# top_3-28-21m.net
KiCad netlist of a schematic drawn in EAGLE
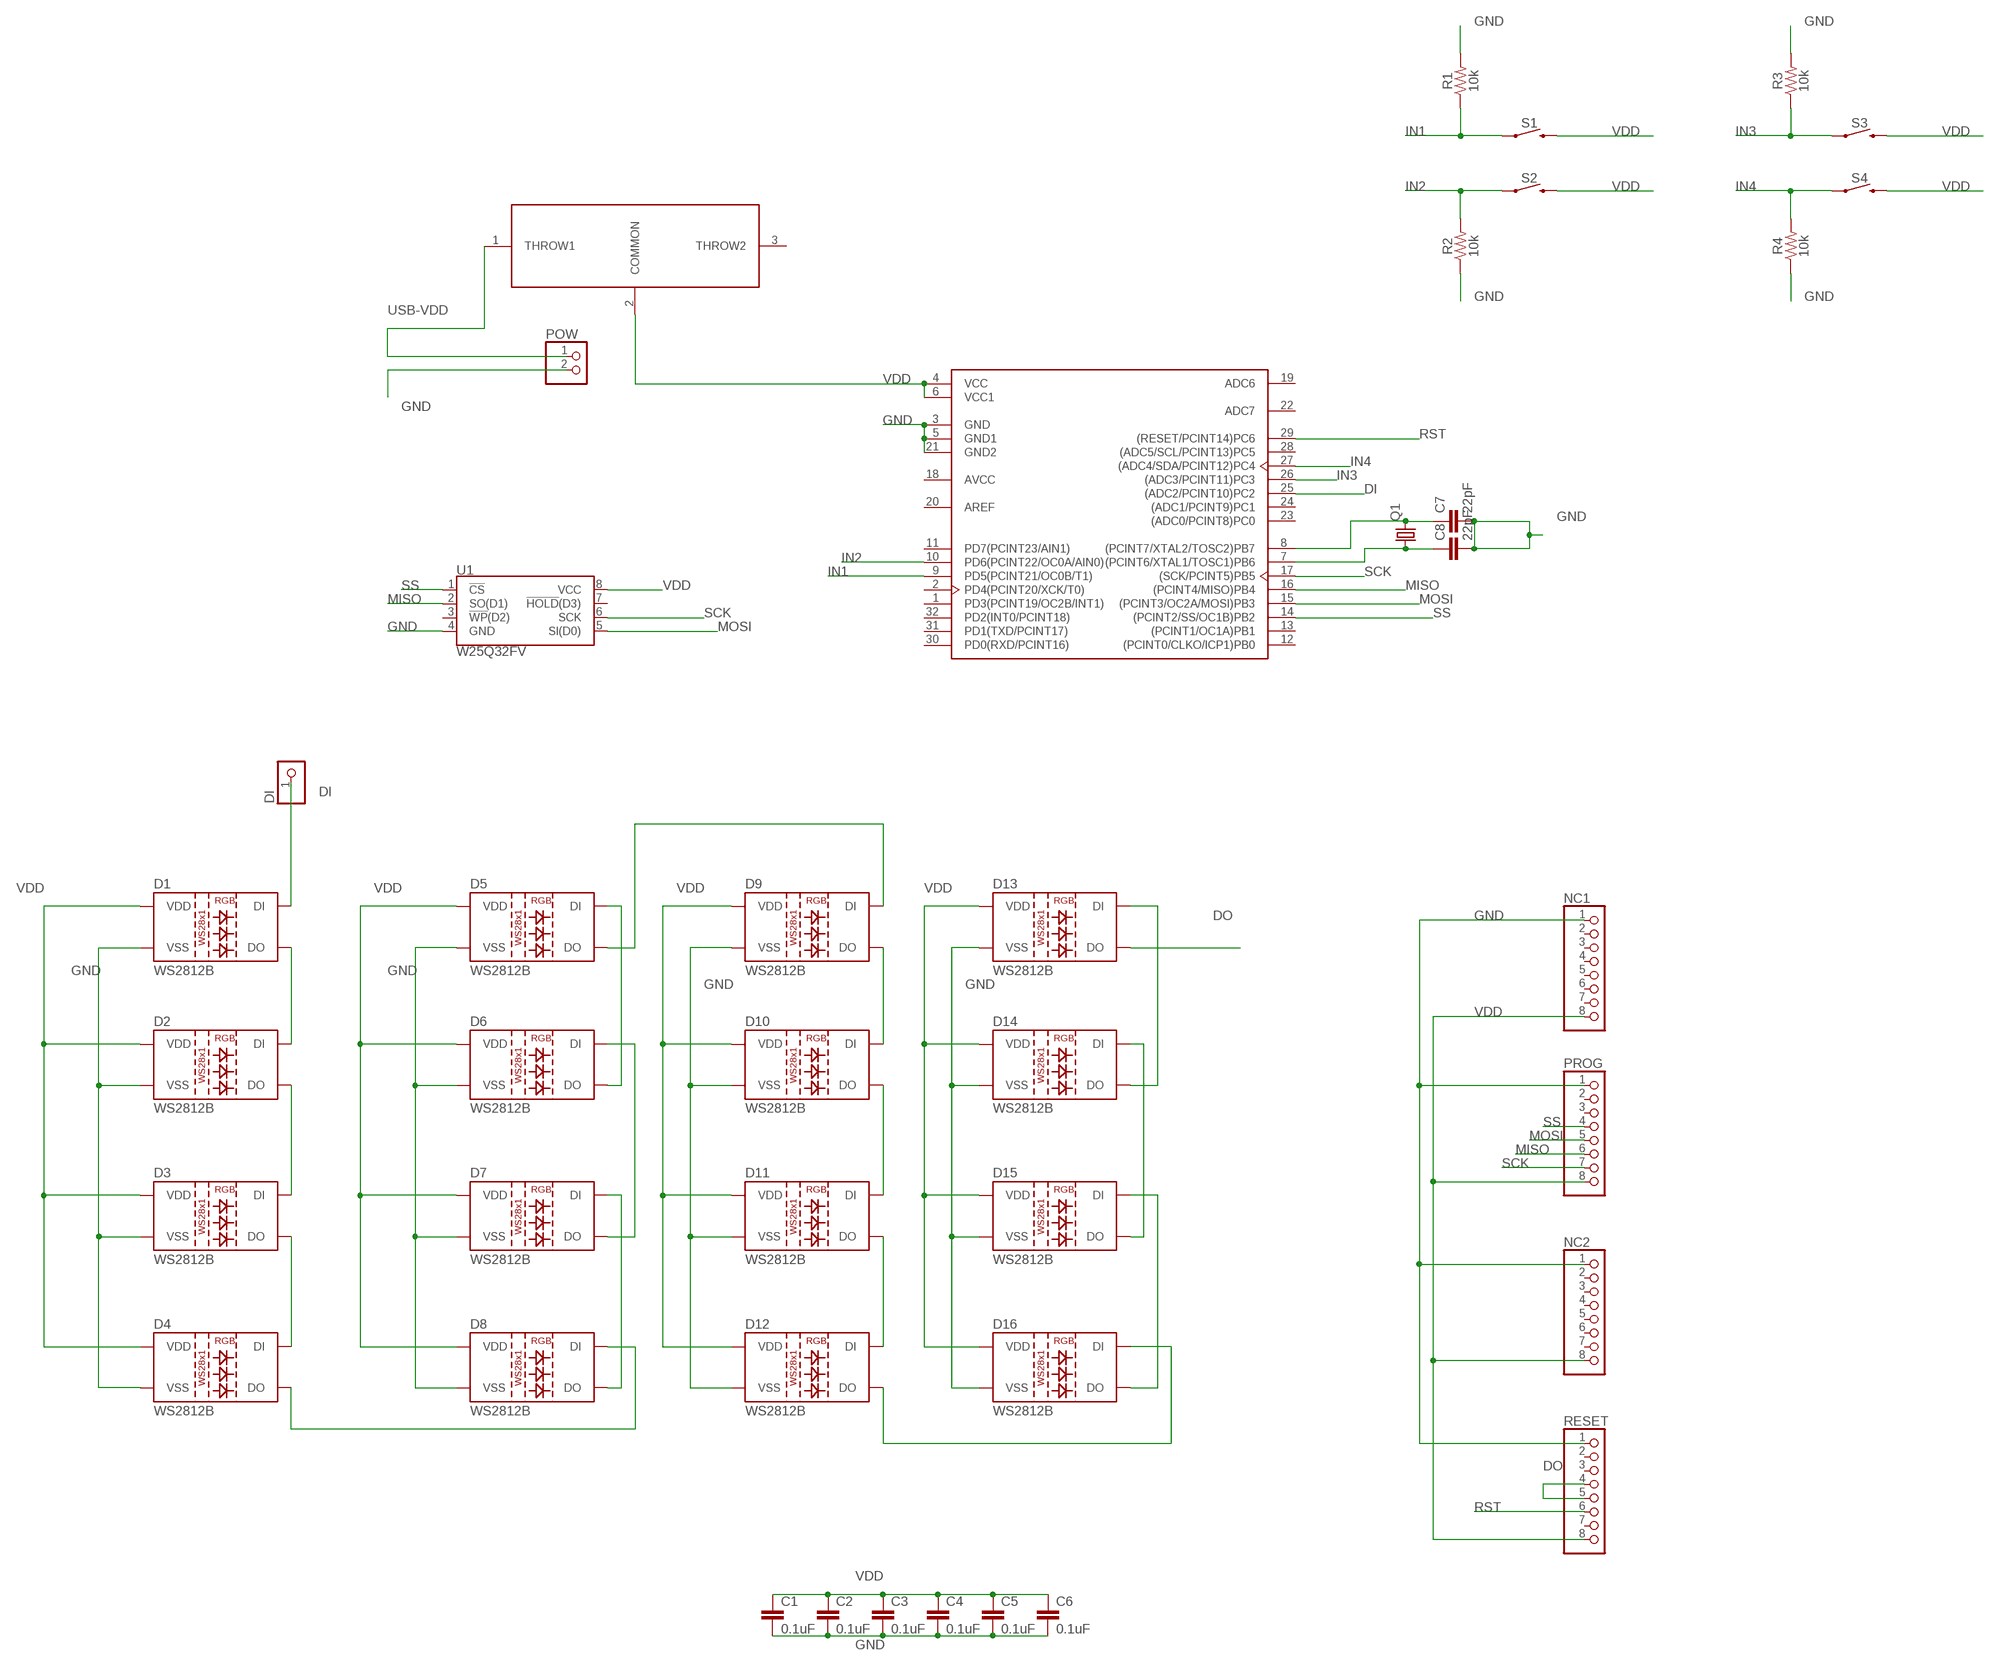
[diagram p0: schematic, sheet 1]

(export (version "E")
  (design (tool "Eeschema 10.0.6"))
  (components
    (comp (ref "C1")
      (value "0.1uF")
      (footprint "eagle-import:0603")
      (libsource (lib "eagle-import") (part "0.1UF-0603-25V-5%"))
    )
    (comp (ref "C2")
      (value "0.1uF")
      (footprint "eagle-import:0603")
      (libsource (lib "eagle-import") (part "0.1UF-0603-25V-5%"))
    )
    (comp (ref "C3")
      (value "0.1uF")
      (footprint "eagle-import:0603")
      (libsource (lib "eagle-import") (part "0.1UF-0603-25V-5%"))
    )
    (comp (ref "C4")
      (value "0.1uF")
      (footprint "eagle-import:0603")
      (libsource (lib "eagle-import") (part "0.1UF-0603-25V-5%"))
    )
    (comp (ref "C5")
      (value "0.1uF")
      (footprint "eagle-import:0603")
      (libsource (lib "eagle-import") (part "0.1UF-0603-25V-5%"))
    )
    (comp (ref "C6")
      (value "0.1uF")
      (footprint "eagle-import:0603")
      (libsource (lib "eagle-import") (part "0.1UF-0603-25V-5%"))
    )
    (comp (ref "C7")
      (value "22pF")
      (footprint "eagle-import:0805")
      (libsource (lib "eagle-import") (part "1.0UF-0805-25V-(+80/-20%)"))
    )
    (comp (ref "C8")
      (value "22pF")
      (footprint "eagle-import:0805")
      (libsource (lib "eagle-import") (part "1.0UF-0805-25V-(+80/-20%)"))
    )
    (comp (ref "D1")
      (value "WS2812B")
      (footprint "eagle-import:WS2812B")
      (libsource (lib "eagle-import") (part "WS2812B"))
    )
    (comp (ref "D2")
      (value "WS2812B")
      (footprint "eagle-import:WS2812B")
      (libsource (lib "eagle-import") (part "WS2812B"))
    )
    (comp (ref "D3")
      (value "WS2812B")
      (footprint "eagle-import:WS2812B")
      (libsource (lib "eagle-import") (part "WS2812B"))
    )
    (comp (ref "D4")
      (value "WS2812B")
      (footprint "eagle-import:WS2812B")
      (libsource (lib "eagle-import") (part "WS2812B"))
    )
    (comp (ref "D5")
      (value "WS2812B")
      (footprint "eagle-import:WS2812B")
      (libsource (lib "eagle-import") (part "WS2812B"))
    )
    (comp (ref "D6")
      (value "WS2812B")
      (footprint "eagle-import:WS2812B")
      (libsource (lib "eagle-import") (part "WS2812B"))
    )
    (comp (ref "D7")
      (value "WS2812B")
      (footprint "eagle-import:WS2812B")
      (libsource (lib "eagle-import") (part "WS2812B"))
    )
    (comp (ref "D8")
      (value "WS2812B")
      (footprint "eagle-import:WS2812B")
      (libsource (lib "eagle-import") (part "WS2812B"))
    )
    (comp (ref "D9")
      (value "WS2812B")
      (footprint "eagle-import:WS2812B")
      (libsource (lib "eagle-import") (part "WS2812B"))
    )
    (comp (ref "D10")
      (value "WS2812B")
      (footprint "eagle-import:WS2812B")
      (libsource (lib "eagle-import") (part "WS2812B"))
    )
    (comp (ref "D11")
      (value "WS2812B")
      (footprint "eagle-import:WS2812B")
      (libsource (lib "eagle-import") (part "WS2812B"))
    )
    (comp (ref "D12")
      (value "WS2812B")
      (footprint "eagle-import:WS2812B")
      (libsource (lib "eagle-import") (part "WS2812B"))
    )
    (comp (ref "D13")
      (value "WS2812B")
      (footprint "eagle-import:WS2812B")
      (libsource (lib "eagle-import") (part "WS2812B"))
    )
    (comp (ref "D14")
      (value "WS2812B")
      (footprint "eagle-import:WS2812B")
      (libsource (lib "eagle-import") (part "WS2812B"))
    )
    (comp (ref "D15")
      (value "WS2812B")
      (footprint "eagle-import:WS2812B")
      (libsource (lib "eagle-import") (part "WS2812B"))
    )
    (comp (ref "D16")
      (value "WS2812B")
      (footprint "eagle-import:WS2812B")
      (libsource (lib "eagle-import") (part "WS2812B"))
    )
    (comp (ref "DI")
      (value "PINHD-1X1")
      (footprint "eagle-import:1X01")
      (libsource (lib "eagle-import") (part "PINHD-1X1"))
    )
    (comp (ref "IC1")
      (value "ATMEGA328P-AU")
      (footprint "eagle-import:TQFP-32")
      (fields
        (field (name "DIGIKEY_PART_NUMBER") "ATMEGA328P-AU-ND")
        (field (name "MANUFACTURER") "Microchip Technology")
        (field (name "CREATED_BY") "PCBLayout.com")
      )
      (libsource (lib "eagle-import") (part "ATMEGA328P-AU"))
    )
    (comp (ref "NC1")
      (value "PINHD-1X8")
      (footprint "eagle-import:1X08")
      (libsource (lib "eagle-import") (part "PINHD-1X8"))
    )
    (comp (ref "NC2")
      (value "PINHD-1X8")
      (footprint "eagle-import:1X08")
      (libsource (lib "eagle-import") (part "PINHD-1X8"))
    )
    (comp (ref "POW")
      (value "PINHD-1X2")
      (footprint "eagle-import:1X02")
      (libsource (lib "eagle-import") (part "PINHD-1X2"))
    )
    (comp (ref "PROG")
      (value "PINHD-1X8")
      (footprint "eagle-import:1X08")
      (libsource (lib "eagle-import") (part "PINHD-1X8"))
    )
    (comp (ref "Q1")
      (value "CRYSTALHC49S")
      (footprint "eagle-import:HC49_S")
      (libsource (lib "eagle-import") (part "CRYSTALHC49S"))
    )
    (comp (ref "R1")
      (value "10k")
      (footprint "eagle-import:0805")
      (libsource (lib "eagle-import") (part "0.3OHM-0805-1/8W-1%"))
    )
    (comp (ref "R2")
      (value "10k")
      (footprint "eagle-import:0805")
      (libsource (lib "eagle-import") (part "0.3OHM-0805-1/8W-1%"))
    )
    (comp (ref "R3")
      (value "10k")
      (footprint "eagle-import:0805")
      (libsource (lib "eagle-import") (part "0.3OHM-0805-1/8W-1%"))
    )
    (comp (ref "R4")
      (value "10k")
      (footprint "eagle-import:0805")
      (libsource (lib "eagle-import") (part "0.3OHM-0805-1/8W-1%"))
    )
    (comp (ref "RESET")
      (value "PINHD-1X8")
      (footprint "eagle-import:1X08")
      (libsource (lib "eagle-import") (part "PINHD-1X8"))
    )
    (comp (ref "S1")
      (value "MOMENTARY-SWITCH-SPST-PTH-6.0MM")
      (footprint "eagle-import:TACTILE_SWITCH_PTH_6.0MM")
      (libsource (lib "eagle-import") (part "MOMENTARY-SWITCH-SPST-PTH-6.0MM"))
    )
    (comp (ref "S2")
      (value "MOMENTARY-SWITCH-SPST-PTH-6.0MM")
      (footprint "eagle-import:TACTILE_SWITCH_PTH_6.0MM")
      (libsource (lib "eagle-import") (part "MOMENTARY-SWITCH-SPST-PTH-6.0MM"))
    )
    (comp (ref "S3")
      (value "MOMENTARY-SWITCH-SPST-PTH-6.0MM")
      (footprint "eagle-import:TACTILE_SWITCH_PTH_6.0MM")
      (libsource (lib "eagle-import") (part "MOMENTARY-SWITCH-SPST-PTH-6.0MM"))
    )
    (comp (ref "S4")
      (value "MOMENTARY-SWITCH-SPST-PTH-6.0MM")
      (footprint "eagle-import:TACTILE_SWITCH_PTH_6.0MM")
      (libsource (lib "eagle-import") (part "MOMENTARY-SWITCH-SPST-PTH-6.0MM"))
    )
    (comp (ref "U$2")
      (value "SLIDE_SWITCH_1P2T")
      (footprint "eagle-import:SLIDE_SWITCH_1P2T")
      (libsource (lib "eagle-import") (part "SLIDE_SWITCH_1P2T"))
    )
    (comp (ref "U1")
      (value "W25Q32FV")
      (footprint "eagle-import:SOIC-8")
      (libsource (lib "eagle-import") (part "W25Q32FVSS"))
    )
  )
  (nets
    (net (code "1") (name "/AREF") (class "Default")
      (node (ref "IC1") (pin "20") (pinfunction "AREF_20") (pintype "power_in"))
    )
    (net (code "2") (name "/AVCC") (class "Default")
      (node (ref "IC1") (pin "18") (pinfunction "AVCC_18") (pintype "power_in"))
    )
    (net (code "3") (name "/DI") (class "Default")
      (node (ref "D1") (pin "4") (pinfunction "DI_4") (pintype "bidirectional"))
      (node (ref "DI") (pin "1") (pinfunction "1_1") (pintype "passive"))
      (node (ref "IC1") (pin "25") (pinfunction "(ADC2/PCINT10)PC2_25") (pintype "bidirectional"))
    )
    (net (code "4") (name "/DO") (class "Default")
      (node (ref "D13") (pin "2") (pinfunction "DO_2") (pintype "bidirectional"))
      (node (ref "RESET") (pin "4") (pinfunction "4_4") (pintype "passive"))
      (node (ref "RESET") (pin "5") (pinfunction "5_5") (pintype "passive"))
    )
    (net (code "5") (name "/GND") (class "Default")
      (node (ref "C1") (pin "2") (pinfunction "2_2") (pintype "passive"))
      (node (ref "C2") (pin "2") (pinfunction "2_2") (pintype "passive"))
      (node (ref "C3") (pin "2") (pinfunction "2_2") (pintype "passive"))
      (node (ref "C4") (pin "2") (pinfunction "2_2") (pintype "passive"))
      (node (ref "C5") (pin "2") (pinfunction "2_2") (pintype "passive"))
      (node (ref "C6") (pin "2") (pinfunction "2_2") (pintype "passive"))
      (node (ref "C7") (pin "2") (pinfunction "2_2") (pintype "passive"))
      (node (ref "C8") (pin "2") (pinfunction "2_2") (pintype "passive"))
      (node (ref "D1") (pin "3") (pinfunction "VSS_3") (pintype "bidirectional"))
      (node (ref "D10") (pin "3") (pinfunction "VSS_3") (pintype "bidirectional"))
      (node (ref "D11") (pin "3") (pinfunction "VSS_3") (pintype "bidirectional"))
      (node (ref "D12") (pin "3") (pinfunction "VSS_3") (pintype "bidirectional"))
      (node (ref "D13") (pin "3") (pinfunction "VSS_3") (pintype "bidirectional"))
      (node (ref "D14") (pin "3") (pinfunction "VSS_3") (pintype "bidirectional"))
      (node (ref "D15") (pin "3") (pinfunction "VSS_3") (pintype "bidirectional"))
      (node (ref "D16") (pin "3") (pinfunction "VSS_3") (pintype "bidirectional"))
      (node (ref "D2") (pin "3") (pinfunction "VSS_3") (pintype "bidirectional"))
      (node (ref "D3") (pin "3") (pinfunction "VSS_3") (pintype "bidirectional"))
      (node (ref "D4") (pin "3") (pinfunction "VSS_3") (pintype "bidirectional"))
      (node (ref "D5") (pin "3") (pinfunction "VSS_3") (pintype "bidirectional"))
      (node (ref "D6") (pin "3") (pinfunction "VSS_3") (pintype "bidirectional"))
      (node (ref "D7") (pin "3") (pinfunction "VSS_3") (pintype "bidirectional"))
      (node (ref "D8") (pin "3") (pinfunction "VSS_3") (pintype "bidirectional"))
      (node (ref "D9") (pin "3") (pinfunction "VSS_3") (pintype "bidirectional"))
      (node (ref "IC1") (pin "21") (pinfunction "GND2_21") (pintype "power_in"))
      (node (ref "IC1") (pin "3") (pinfunction "GND_3") (pintype "power_in"))
      (node (ref "IC1") (pin "5") (pinfunction "GND1_5") (pintype "power_in"))
      (node (ref "NC1") (pin "1") (pinfunction "1_1") (pintype "passive"))
      (node (ref "NC2") (pin "1") (pinfunction "1_1") (pintype "passive"))
      (node (ref "POW") (pin "2") (pinfunction "2_2") (pintype "passive"))
      (node (ref "PROG") (pin "1") (pinfunction "1_1") (pintype "passive"))
      (node (ref "R1") (pin "2") (pinfunction "2_2") (pintype "passive"))
      (node (ref "R2") (pin "1") (pinfunction "1_1") (pintype "passive"))
      (node (ref "R3") (pin "2") (pinfunction "2_2") (pintype "passive"))
      (node (ref "R4") (pin "1") (pinfunction "1_1") (pintype "passive"))
      (node (ref "RESET") (pin "1") (pinfunction "1_1") (pintype "passive"))
      (node (ref "U1") (pin "4") (pinfunction "GND_4") (pintype "bidirectional"))
    )
    (net (code "6") (name "/IN1") (class "Default")
      (node (ref "IC1") (pin "9") (pinfunction "PD5(PCINT21/OC0B/T1)_9") (pintype "bidirectional"))
      (node (ref "R1") (pin "1") (pinfunction "1_1") (pintype "passive"))
      (node (ref "S1") (pin "1") (pinfunction "1_1") (pintype "passive"))
    )
    (net (code "7") (name "/IN2") (class "Default")
      (node (ref "IC1") (pin "10") (pinfunction "PD6(PCINT22/OC0A/AIN0)_10") (pintype "bidirectional"))
      (node (ref "R2") (pin "2") (pinfunction "2_2") (pintype "passive"))
      (node (ref "S2") (pin "1") (pinfunction "1_1") (pintype "passive"))
    )
    (net (code "8") (name "/IN3") (class "Default")
      (node (ref "IC1") (pin "26") (pinfunction "(ADC3/PCINT11)PC3_26") (pintype "bidirectional"))
      (node (ref "R3") (pin "1") (pinfunction "1_1") (pintype "passive"))
      (node (ref "S3") (pin "1") (pinfunction "1_1") (pintype "passive"))
    )
    (net (code "9") (name "/IN4") (class "Default")
      (node (ref "IC1") (pin "27") (pinfunction "(ADC4/SDA/PCINT12)PC4_27") (pintype "bidirectional"))
      (node (ref "R4") (pin "2") (pinfunction "2_2") (pintype "passive"))
      (node (ref "S4") (pin "1") (pinfunction "1_1") (pintype "passive"))
    )
    (net (code "10") (name "/MISO") (class "Default")
      (node (ref "IC1") (pin "16") (pinfunction "(PCINT4/MISO)PB4_16") (pintype "bidirectional"))
      (node (ref "PROG") (pin "6") (pinfunction "6_6") (pintype "passive"))
      (node (ref "U1") (pin "2") (pinfunction "SO(D1)_2") (pintype "bidirectional"))
    )
    (net (code "11") (name "/MOSI") (class "Default")
      (node (ref "IC1") (pin "15") (pinfunction "(PCINT3/OC2A/MOSI)PB3_15") (pintype "bidirectional"))
      (node (ref "PROG") (pin "5") (pinfunction "5_5") (pintype "passive"))
      (node (ref "U1") (pin "5") (pinfunction "SI(D0)_5") (pintype "bidirectional"))
    )
    (net (code "12") (name "/RST") (class "Default")
      (node (ref "IC1") (pin "29") (pinfunction "(RESET/PCINT14)PC6_29") (pintype "bidirectional"))
      (node (ref "RESET") (pin "6") (pinfunction "6_6") (pintype "passive"))
    )
    (net (code "13") (name "/SCK") (class "Default")
      (node (ref "IC1") (pin "17") (pinfunction "(SCK/PCINT5)PB5_17") (pintype "bidirectional"))
      (node (ref "PROG") (pin "7") (pinfunction "7_7") (pintype "passive"))
      (node (ref "U1") (pin "6") (pinfunction "SCK_6") (pintype "bidirectional"))
    )
    (net (code "14") (name "/SS") (class "Default")
      (node (ref "IC1") (pin "14") (pinfunction "(PCINT2/SS/OC1B)PB2_14") (pintype "bidirectional"))
      (node (ref "PROG") (pin "4") (pinfunction "4_4") (pintype "passive"))
      (node (ref "U1") (pin "1") (pinfunction "~{CS}_1") (pintype "bidirectional"))
    )
    (net (code "15") (name "/USB-VDD") (class "Default")
      (node (ref "POW") (pin "1") (pinfunction "1_1") (pintype "passive"))
      (node (ref "U$2") (pin "1") (pinfunction "THROW1_1") (pintype "bidirectional"))
    )
    (net (code "16") (name "/VDD") (class "Default")
      (node (ref "C1") (pin "1") (pinfunction "1_1") (pintype "passive"))
      (node (ref "C2") (pin "1") (pinfunction "1_1") (pintype "passive"))
      (node (ref "C3") (pin "1") (pinfunction "1_1") (pintype "passive"))
      (node (ref "C4") (pin "1") (pinfunction "1_1") (pintype "passive"))
      (node (ref "C5") (pin "1") (pinfunction "1_1") (pintype "passive"))
      (node (ref "C6") (pin "1") (pinfunction "1_1") (pintype "passive"))
      (node (ref "D1") (pin "1") (pinfunction "VDD_1") (pintype "bidirectional"))
      (node (ref "D10") (pin "1") (pinfunction "VDD_1") (pintype "bidirectional"))
      (node (ref "D11") (pin "1") (pinfunction "VDD_1") (pintype "bidirectional"))
      (node (ref "D12") (pin "1") (pinfunction "VDD_1") (pintype "bidirectional"))
      (node (ref "D13") (pin "1") (pinfunction "VDD_1") (pintype "bidirectional"))
      (node (ref "D14") (pin "1") (pinfunction "VDD_1") (pintype "bidirectional"))
      (node (ref "D15") (pin "1") (pinfunction "VDD_1") (pintype "bidirectional"))
      (node (ref "D16") (pin "1") (pinfunction "VDD_1") (pintype "bidirectional"))
      (node (ref "D2") (pin "1") (pinfunction "VDD_1") (pintype "bidirectional"))
      (node (ref "D3") (pin "1") (pinfunction "VDD_1") (pintype "bidirectional"))
      (node (ref "D4") (pin "1") (pinfunction "VDD_1") (pintype "bidirectional"))
      (node (ref "D5") (pin "1") (pinfunction "VDD_1") (pintype "bidirectional"))
      (node (ref "D6") (pin "1") (pinfunction "VDD_1") (pintype "bidirectional"))
      (node (ref "D7") (pin "1") (pinfunction "VDD_1") (pintype "bidirectional"))
      (node (ref "D8") (pin "1") (pinfunction "VDD_1") (pintype "bidirectional"))
      (node (ref "D9") (pin "1") (pinfunction "VDD_1") (pintype "bidirectional"))
      (node (ref "IC1") (pin "4") (pinfunction "VCC_4") (pintype "power_in"))
      (node (ref "IC1") (pin "6") (pinfunction "VCC1_6") (pintype "power_in"))
      (node (ref "NC1") (pin "8") (pinfunction "8_8") (pintype "passive"))
      (node (ref "NC2") (pin "8") (pinfunction "8_8") (pintype "passive"))
      (node (ref "PROG") (pin "8") (pinfunction "8_8") (pintype "passive"))
      (node (ref "RESET") (pin "8") (pinfunction "8_8") (pintype "passive"))
      (node (ref "S1") (pin "3") (pinfunction "2_3") (pintype "passive"))
      (node (ref "S2") (pin "3") (pinfunction "2_3") (pintype "passive"))
      (node (ref "S3") (pin "3") (pinfunction "2_3") (pintype "passive"))
      (node (ref "S4") (pin "3") (pinfunction "2_3") (pintype "passive"))
      (node (ref "U$2") (pin "2") (pinfunction "COMMON_2") (pintype "bidirectional"))
      (node (ref "U1") (pin "8") (pinfunction "VCC_8") (pintype "bidirectional"))
    )
    (net (code "17") (name "Net-(D1-DO)") (class "Default")
      (node (ref "D1") (pin "2") (pinfunction "DO_2") (pintype "bidirectional"))
      (node (ref "D2") (pin "4") (pinfunction "DI_4") (pintype "bidirectional"))
    )
    (net (code "18") (name "Net-(D2-DO)") (class "Default")
      (node (ref "D2") (pin "2") (pinfunction "DO_2") (pintype "bidirectional"))
      (node (ref "D3") (pin "4") (pinfunction "DI_4") (pintype "bidirectional"))
    )
    (net (code "19") (name "Net-(D3-DO)") (class "Default")
      (node (ref "D3") (pin "2") (pinfunction "DO_2") (pintype "bidirectional"))
      (node (ref "D4") (pin "4") (pinfunction "DI_4") (pintype "bidirectional"))
    )
    (net (code "20") (name "Net-(D4-DO)") (class "Default")
      (node (ref "D4") (pin "2") (pinfunction "DO_2") (pintype "bidirectional"))
      (node (ref "D8") (pin "4") (pinfunction "DI_4") (pintype "bidirectional"))
    )
    (net (code "21") (name "Net-(D5-DI)") (class "Default")
      (node (ref "D5") (pin "4") (pinfunction "DI_4") (pintype "bidirectional"))
      (node (ref "D6") (pin "2") (pinfunction "DO_2") (pintype "bidirectional"))
    )
    (net (code "22") (name "Net-(D5-DO)") (class "Default")
      (node (ref "D5") (pin "2") (pinfunction "DO_2") (pintype "bidirectional"))
      (node (ref "D9") (pin "4") (pinfunction "DI_4") (pintype "bidirectional"))
    )
    (net (code "23") (name "Net-(D6-DI)") (class "Default")
      (node (ref "D6") (pin "4") (pinfunction "DI_4") (pintype "bidirectional"))
      (node (ref "D7") (pin "2") (pinfunction "DO_2") (pintype "bidirectional"))
    )
    (net (code "24") (name "Net-(D7-DI)") (class "Default")
      (node (ref "D7") (pin "4") (pinfunction "DI_4") (pintype "bidirectional"))
      (node (ref "D8") (pin "2") (pinfunction "DO_2") (pintype "bidirectional"))
    )
    (net (code "25") (name "Net-(D10-DI)") (class "Default")
      (node (ref "D10") (pin "4") (pinfunction "DI_4") (pintype "bidirectional"))
      (node (ref "D9") (pin "2") (pinfunction "DO_2") (pintype "bidirectional"))
    )
    (net (code "26") (name "Net-(D10-DO)") (class "Default")
      (node (ref "D10") (pin "2") (pinfunction "DO_2") (pintype "bidirectional"))
      (node (ref "D11") (pin "4") (pinfunction "DI_4") (pintype "bidirectional"))
    )
    (net (code "27") (name "Net-(D11-DO)") (class "Default")
      (node (ref "D11") (pin "2") (pinfunction "DO_2") (pintype "bidirectional"))
      (node (ref "D12") (pin "4") (pinfunction "DI_4") (pintype "bidirectional"))
    )
    (net (code "28") (name "Net-(D12-DO)") (class "Default")
      (node (ref "D12") (pin "2") (pinfunction "DO_2") (pintype "bidirectional"))
      (node (ref "D16") (pin "4") (pinfunction "DI_4") (pintype "bidirectional"))
    )
    (net (code "29") (name "Net-(D13-DI)") (class "Default")
      (node (ref "D13") (pin "4") (pinfunction "DI_4") (pintype "bidirectional"))
      (node (ref "D14") (pin "2") (pinfunction "DO_2") (pintype "bidirectional"))
    )
    (net (code "30") (name "Net-(D14-DI)") (class "Default")
      (node (ref "D14") (pin "4") (pinfunction "DI_4") (pintype "bidirectional"))
      (node (ref "D15") (pin "2") (pinfunction "DO_2") (pintype "bidirectional"))
    )
    (net (code "31") (name "Net-(D15-DI)") (class "Default")
      (node (ref "D15") (pin "4") (pinfunction "DI_4") (pintype "bidirectional"))
      (node (ref "D16") (pin "2") (pinfunction "DO_2") (pintype "bidirectional"))
    )
    (net (code "32") (name "Net-(IC1-(PCINT6{slash}XTAL1{slash}TOSC1)PB6)") (class "Default")
      (node (ref "C8") (pin "1") (pinfunction "1_1") (pintype "passive"))
      (node (ref "IC1") (pin "7") (pinfunction "(PCINT6/XTAL1/TOSC1)PB6_7") (pintype "bidirectional"))
      (node (ref "Q1") (pin "1") (pinfunction "1_1") (pintype "passive"))
    )
    (net (code "33") (name "Net-(IC1-(PCINT7{slash}XTAL2{slash}TOSC2)PB7)") (class "Default")
      (node (ref "C7") (pin "1") (pinfunction "1_1") (pintype "passive"))
      (node (ref "IC1") (pin "8") (pinfunction "(PCINT7/XTAL2/TOSC2)PB7_8") (pintype "bidirectional"))
      (node (ref "Q1") (pin "2") (pinfunction "2_2") (pintype "passive"))
    )
    (net (code "34") (name "unconnected-(IC1-(ADC0{slash}PCINT8)PC0-Pad23)") (class "Default")
      (node (ref "IC1") (pin "23") (pinfunction "(ADC0/PCINT8)PC0_23") (pintype "bidirectional"))
    )
    (net (code "35") (name "unconnected-(IC1-(ADC1{slash}PCINT9)PC1-Pad24)") (class "Default")
      (node (ref "IC1") (pin "24") (pinfunction "(ADC1/PCINT9)PC1_24") (pintype "bidirectional"))
    )
    (net (code "36") (name "unconnected-(IC1-(ADC5{slash}SCL{slash}PCINT13)PC5-Pad28)") (class "Default")
      (node (ref "IC1") (pin "28") (pinfunction "(ADC5/SCL/PCINT13)PC5_28") (pintype "bidirectional"))
    )
    (net (code "37") (name "unconnected-(IC1-(PCINT0{slash}CLKO{slash}ICP1)PB0-Pad12)") (class "Default")
      (node (ref "IC1") (pin "12") (pinfunction "(PCINT0/CLKO/ICP1)PB0_12") (pintype "bidirectional"))
    )
    (net (code "38") (name "unconnected-(IC1-(PCINT1{slash}OC1A)PB1-Pad13)") (class "Default")
      (node (ref "IC1") (pin "13") (pinfunction "(PCINT1/OC1A)PB1_13") (pintype "bidirectional"))
    )
    (net (code "39") (name "unconnected-(IC1-ADC6-Pad19)") (class "Default")
      (node (ref "IC1") (pin "19") (pinfunction "ADC6_19") (pintype "input"))
    )
    (net (code "40") (name "unconnected-(IC1-ADC7-Pad22)") (class "Default")
      (node (ref "IC1") (pin "22") (pinfunction "ADC7_22") (pintype "input"))
    )
    (net (code "41") (name "unconnected-(IC1-PD0(RXD{slash}PCINT16)-Pad30)") (class "Default")
      (node (ref "IC1") (pin "30") (pinfunction "PD0(RXD/PCINT16)_30") (pintype "bidirectional"))
    )
    (net (code "42") (name "unconnected-(IC1-PD1(TXD{slash}PCINT17)-Pad31)") (class "Default")
      (node (ref "IC1") (pin "31") (pinfunction "PD1(TXD/PCINT17)_31") (pintype "bidirectional"))
    )
    (net (code "43") (name "unconnected-(IC1-PD2(INT0{slash}PCINT18)-Pad32)") (class "Default")
      (node (ref "IC1") (pin "32") (pinfunction "PD2(INT0/PCINT18)_32") (pintype "bidirectional"))
    )
    (net (code "44") (name "unconnected-(IC1-PD3(PCINT19{slash}OC2B{slash}INT1)-Pad1)") (class "Default")
      (node (ref "IC1") (pin "1") (pinfunction "PD3(PCINT19/OC2B/INT1)_1") (pintype "bidirectional"))
    )
    (net (code "45") (name "unconnected-(IC1-PD4(PCINT20{slash}XCK{slash}T0)-Pad2)") (class "Default")
      (node (ref "IC1") (pin "2") (pinfunction "PD4(PCINT20/XCK/T0)_2") (pintype "bidirectional"))
    )
    (net (code "46") (name "unconnected-(IC1-PD7(PCINT23{slash}AIN1)-Pad11)") (class "Default")
      (node (ref "IC1") (pin "11") (pinfunction "PD7(PCINT23/AIN1)_11") (pintype "bidirectional"))
    )
    (net (code "47") (name "unconnected-(NC1-Pad2)") (class "Default")
      (node (ref "NC1") (pin "2") (pinfunction "2_2") (pintype "passive"))
    )
    (net (code "48") (name "unconnected-(NC1-Pad3)") (class "Default")
      (node (ref "NC1") (pin "3") (pinfunction "3_3") (pintype "passive"))
    )
    (net (code "49") (name "unconnected-(NC1-Pad4)") (class "Default")
      (node (ref "NC1") (pin "4") (pinfunction "4_4") (pintype "passive"))
    )
    (net (code "50") (name "unconnected-(NC1-Pad5)") (class "Default")
      (node (ref "NC1") (pin "5") (pinfunction "5_5") (pintype "passive"))
    )
    (net (code "51") (name "unconnected-(NC1-Pad6)") (class "Default")
      (node (ref "NC1") (pin "6") (pinfunction "6_6") (pintype "passive"))
    )
    (net (code "52") (name "unconnected-(NC1-Pad7)") (class "Default")
      (node (ref "NC1") (pin "7") (pinfunction "7_7") (pintype "passive"))
    )
    (net (code "53") (name "unconnected-(NC2-Pad2)") (class "Default")
      (node (ref "NC2") (pin "2") (pinfunction "2_2") (pintype "passive"))
    )
    (net (code "54") (name "unconnected-(NC2-Pad3)") (class "Default")
      (node (ref "NC2") (pin "3") (pinfunction "3_3") (pintype "passive"))
    )
    (net (code "55") (name "unconnected-(NC2-Pad4)") (class "Default")
      (node (ref "NC2") (pin "4") (pinfunction "4_4") (pintype "passive"))
    )
    (net (code "56") (name "unconnected-(NC2-Pad5)") (class "Default")
      (node (ref "NC2") (pin "5") (pinfunction "5_5") (pintype "passive"))
    )
    (net (code "57") (name "unconnected-(NC2-Pad6)") (class "Default")
      (node (ref "NC2") (pin "6") (pinfunction "6_6") (pintype "passive"))
    )
    (net (code "58") (name "unconnected-(NC2-Pad7)") (class "Default")
      (node (ref "NC2") (pin "7") (pinfunction "7_7") (pintype "passive"))
    )
    (net (code "59") (name "unconnected-(PROG-Pad2)") (class "Default")
      (node (ref "PROG") (pin "2") (pinfunction "2_2") (pintype "passive"))
    )
    (net (code "60") (name "unconnected-(PROG-Pad3)") (class "Default")
      (node (ref "PROG") (pin "3") (pinfunction "3_3") (pintype "passive"))
    )
    (net (code "61") (name "unconnected-(RESET-Pad2)") (class "Default")
      (node (ref "RESET") (pin "2") (pinfunction "2_2") (pintype "passive"))
    )
    (net (code "62") (name "unconnected-(RESET-Pad3)") (class "Default")
      (node (ref "RESET") (pin "3") (pinfunction "3_3") (pintype "passive"))
    )
    (net (code "63") (name "unconnected-(RESET-Pad7)") (class "Default")
      (node (ref "RESET") (pin "7") (pinfunction "7_7") (pintype "passive"))
    )
    (net (code "64") (name "unconnected-(U$2-THROW2-Pad3)") (class "Default")
      (node (ref "U$2") (pin "3") (pinfunction "THROW2_3") (pintype "bidirectional"))
    )
    (net (code "65") (name "unconnected-(U1-~{HOLD}(D3)-Pad7)") (class "Default")
      (node (ref "U1") (pin "7") (pinfunction "~{HOLD}(D3)_7") (pintype "bidirectional"))
    )
    (net (code "66") (name "unconnected-(U1-~{WP}(D2)-Pad3)") (class "Default")
      (node (ref "U1") (pin "3") (pinfunction "~{WP}(D2)_3") (pintype "bidirectional"))
    )
  )
)
